# in3ator_LEDStrip2.net
KiCad netlist of a schematic drawn in Altium Designer
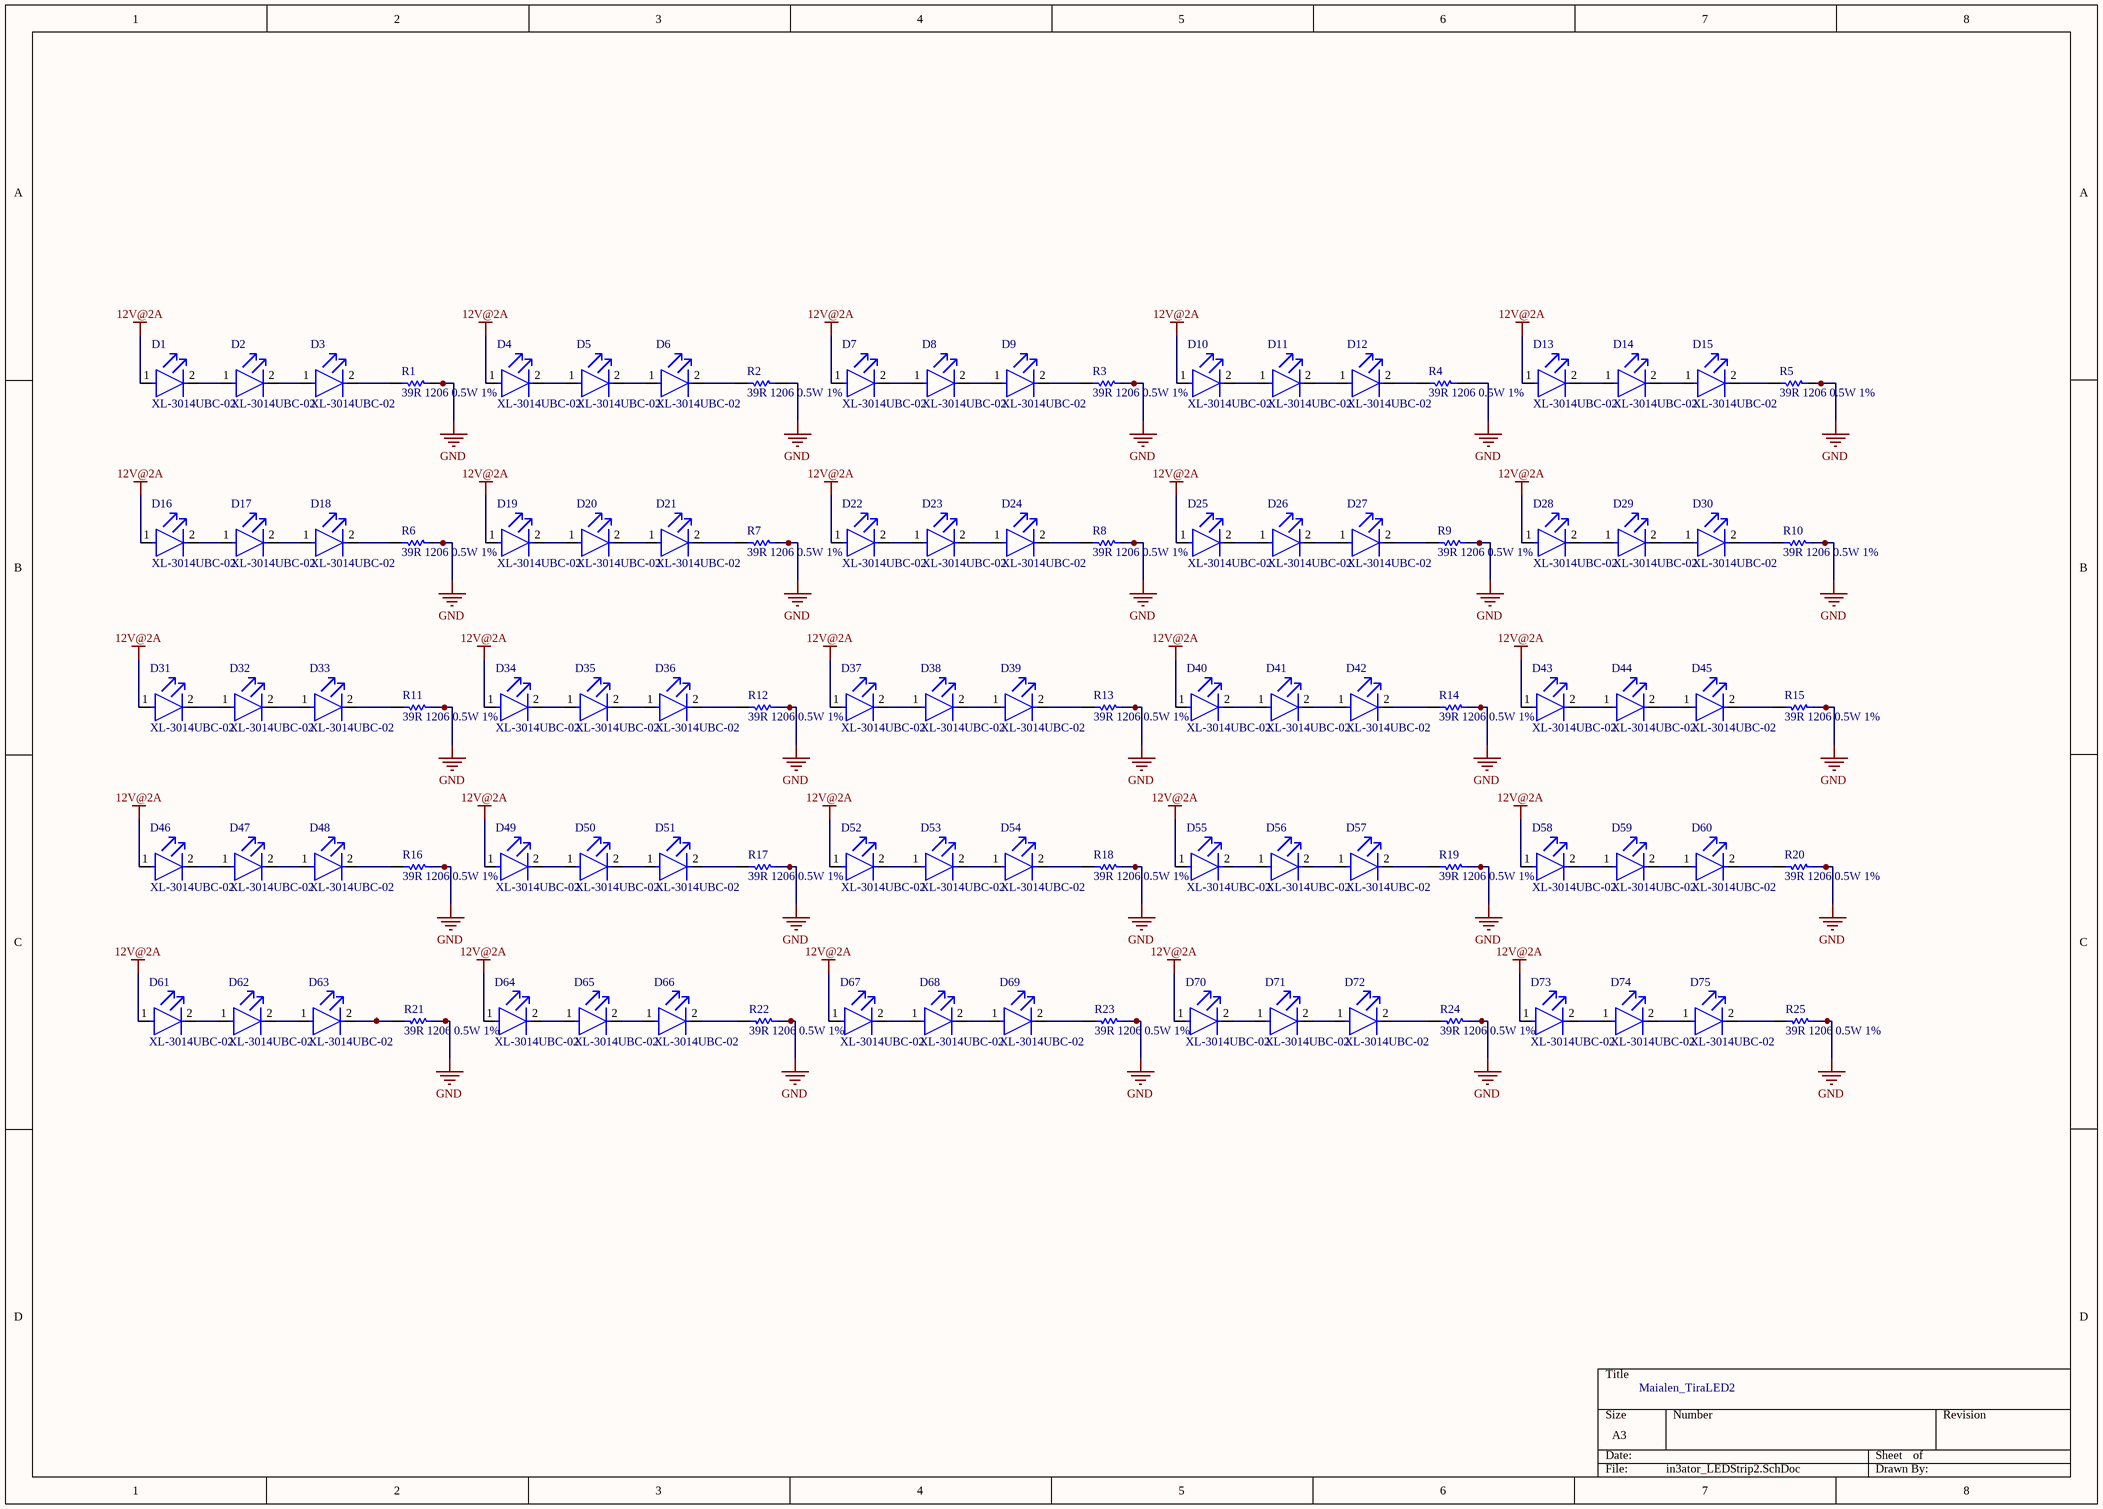
[diagram p0: in3ator_LEDStrip2.SchDoc]

(export (version "E")
  (design (tool "Eeschema 10.0.6"))
  (components
    (comp (ref "D1")
      (value "XL-3014UBC-02")
      (footprint "Diode_led")
      (description "LED GREEN ESS II SMD")
      (fields (field (name "OBSOLETE PART") "true") (field (name "MANUFACTURER") "Panasonic"))
      (libsource (lib "Maialen_TiraLED") (part "CMP-05535-000002-1"))
    )
    (comp (ref "D2")
      (value "XL-3014UBC-02")
      (footprint "Diode_led")
      (description "LED GREEN ESS II SMD")
      (fields (field (name "OBSOLETE PART") "true") (field (name "MANUFACTURER") "Panasonic"))
      (libsource (lib "Maialen_TiraLED") (part "CMP-05535-000002-1"))
    )
    (comp (ref "D3")
      (value "XL-3014UBC-02")
      (footprint "Diode_led")
      (description "LED GREEN ESS II SMD")
      (fields (field (name "OBSOLETE PART") "true") (field (name "MANUFACTURER") "Panasonic"))
      (libsource (lib "Maialen_TiraLED") (part "CMP-05535-000002-1"))
    )
    (comp (ref "D4")
      (value "XL-3014UBC-02")
      (footprint "Diode_led")
      (description "LED GREEN ESS II SMD")
      (fields (field (name "OBSOLETE PART") "true") (field (name "MANUFACTURER") "Panasonic"))
      (libsource (lib "Maialen_TiraLED") (part "CMP-05535-000002-1"))
    )
    (comp (ref "D5")
      (value "XL-3014UBC-02")
      (footprint "Diode_led")
      (description "LED GREEN ESS II SMD")
      (fields (field (name "OBSOLETE PART") "true") (field (name "MANUFACTURER") "Panasonic"))
      (libsource (lib "Maialen_TiraLED") (part "CMP-05535-000002-1"))
    )
    (comp (ref "D6")
      (value "XL-3014UBC-02")
      (footprint "Diode_led")
      (description "LED GREEN ESS II SMD")
      (fields (field (name "OBSOLETE PART") "true") (field (name "MANUFACTURER") "Panasonic"))
      (libsource (lib "Maialen_TiraLED") (part "CMP-05535-000002-1"))
    )
    (comp (ref "D7")
      (value "XL-3014UBC-02")
      (footprint "Diode_led")
      (description "LED GREEN ESS II SMD")
      (fields (field (name "OBSOLETE PART") "true") (field (name "MANUFACTURER") "Panasonic"))
      (libsource (lib "Maialen_TiraLED") (part "CMP-05535-000002-1"))
    )
    (comp (ref "D8")
      (value "XL-3014UBC-02")
      (footprint "Diode_led")
      (description "LED GREEN ESS II SMD")
      (fields (field (name "OBSOLETE PART") "true") (field (name "MANUFACTURER") "Panasonic"))
      (libsource (lib "Maialen_TiraLED") (part "CMP-05535-000002-1"))
    )
    (comp (ref "D9")
      (value "XL-3014UBC-02")
      (footprint "Diode_led")
      (description "LED GREEN ESS II SMD")
      (fields (field (name "OBSOLETE PART") "true") (field (name "MANUFACTURER") "Panasonic"))
      (libsource (lib "Maialen_TiraLED") (part "CMP-05535-000002-1"))
    )
    (comp (ref "D10")
      (value "XL-3014UBC-02")
      (footprint "Diode_led")
      (description "LED GREEN ESS II SMD")
      (fields (field (name "OBSOLETE PART") "true") (field (name "MANUFACTURER") "Panasonic"))
      (libsource (lib "Maialen_TiraLED") (part "CMP-05535-000002-1"))
    )
    (comp (ref "D11")
      (value "XL-3014UBC-02")
      (footprint "Diode_led")
      (description "LED GREEN ESS II SMD")
      (fields (field (name "OBSOLETE PART") "true") (field (name "MANUFACTURER") "Panasonic"))
      (libsource (lib "Maialen_TiraLED") (part "CMP-05535-000002-1"))
    )
    (comp (ref "D12")
      (value "XL-3014UBC-02")
      (footprint "Diode_led")
      (description "LED GREEN ESS II SMD")
      (fields (field (name "OBSOLETE PART") "true") (field (name "MANUFACTURER") "Panasonic"))
      (libsource (lib "Maialen_TiraLED") (part "CMP-05535-000002-1"))
    )
    (comp (ref "D13")
      (value "XL-3014UBC-02")
      (footprint "Diode_led")
      (description "LED GREEN ESS II SMD")
      (fields (field (name "OBSOLETE PART") "true") (field (name "MANUFACTURER") "Panasonic"))
      (libsource (lib "Maialen_TiraLED") (part "CMP-05535-000002-1"))
    )
    (comp (ref "D14")
      (value "XL-3014UBC-02")
      (footprint "Diode_led")
      (description "LED GREEN ESS II SMD")
      (fields (field (name "OBSOLETE PART") "true") (field (name "MANUFACTURER") "Panasonic"))
      (libsource (lib "Maialen_TiraLED") (part "CMP-05535-000002-1"))
    )
    (comp (ref "D15")
      (value "XL-3014UBC-02")
      (footprint "Diode_led")
      (description "LED GREEN ESS II SMD")
      (fields (field (name "OBSOLETE PART") "true") (field (name "MANUFACTURER") "Panasonic"))
      (libsource (lib "Maialen_TiraLED") (part "CMP-05535-000002-1"))
    )
    (comp (ref "D16")
      (value "XL-3014UBC-02")
      (footprint "Diode_led")
      (description "LED GREEN ESS II SMD")
      (fields (field (name "OBSOLETE PART") "true") (field (name "MANUFACTURER") "Panasonic"))
      (libsource (lib "Maialen_TiraLED") (part "CMP-05535-000002-1"))
    )
    (comp (ref "D17")
      (value "XL-3014UBC-02")
      (footprint "Diode_led")
      (description "LED GREEN ESS II SMD")
      (fields (field (name "OBSOLETE PART") "true") (field (name "MANUFACTURER") "Panasonic"))
      (libsource (lib "Maialen_TiraLED") (part "CMP-05535-000002-1"))
    )
    (comp (ref "D18")
      (value "XL-3014UBC-02")
      (footprint "Diode_led")
      (description "LED GREEN ESS II SMD")
      (fields (field (name "OBSOLETE PART") "true") (field (name "MANUFACTURER") "Panasonic"))
      (libsource (lib "Maialen_TiraLED") (part "CMP-05535-000002-1"))
    )
    (comp (ref "D19")
      (value "XL-3014UBC-02")
      (footprint "Diode_led")
      (description "LED GREEN ESS II SMD")
      (fields (field (name "OBSOLETE PART") "true") (field (name "MANUFACTURER") "Panasonic"))
      (libsource (lib "Maialen_TiraLED") (part "CMP-05535-000002-1"))
    )
    (comp (ref "D20")
      (value "XL-3014UBC-02")
      (footprint "Diode_led")
      (description "LED GREEN ESS II SMD")
      (fields (field (name "OBSOLETE PART") "true") (field (name "MANUFACTURER") "Panasonic"))
      (libsource (lib "Maialen_TiraLED") (part "CMP-05535-000002-1"))
    )
    (comp (ref "D21")
      (value "XL-3014UBC-02")
      (footprint "Diode_led")
      (description "LED GREEN ESS II SMD")
      (fields (field (name "OBSOLETE PART") "true") (field (name "MANUFACTURER") "Panasonic"))
      (libsource (lib "Maialen_TiraLED") (part "CMP-05535-000002-1"))
    )
    (comp (ref "D22")
      (value "XL-3014UBC-02")
      (footprint "Diode_led")
      (description "LED GREEN ESS II SMD")
      (fields (field (name "OBSOLETE PART") "true") (field (name "MANUFACTURER") "Panasonic"))
      (libsource (lib "Maialen_TiraLED") (part "CMP-05535-000002-1"))
    )
    (comp (ref "D23")
      (value "XL-3014UBC-02")
      (footprint "Diode_led")
      (description "LED GREEN ESS II SMD")
      (fields (field (name "OBSOLETE PART") "true") (field (name "MANUFACTURER") "Panasonic"))
      (libsource (lib "Maialen_TiraLED") (part "CMP-05535-000002-1"))
    )
    (comp (ref "D24")
      (value "XL-3014UBC-02")
      (footprint "Diode_led")
      (description "LED GREEN ESS II SMD")
      (fields (field (name "OBSOLETE PART") "true") (field (name "MANUFACTURER") "Panasonic"))
      (libsource (lib "Maialen_TiraLED") (part "CMP-05535-000002-1"))
    )
    (comp (ref "D25")
      (value "XL-3014UBC-02")
      (footprint "Diode_led")
      (description "LED GREEN ESS II SMD")
      (fields (field (name "OBSOLETE PART") "true") (field (name "MANUFACTURER") "Panasonic"))
      (libsource (lib "Maialen_TiraLED") (part "CMP-05535-000002-1"))
    )
    (comp (ref "D26")
      (value "XL-3014UBC-02")
      (footprint "Diode_led")
      (description "LED GREEN ESS II SMD")
      (fields (field (name "OBSOLETE PART") "true") (field (name "MANUFACTURER") "Panasonic"))
      (libsource (lib "Maialen_TiraLED") (part "CMP-05535-000002-1"))
    )
    (comp (ref "D27")
      (value "XL-3014UBC-02")
      (footprint "Diode_led")
      (description "LED GREEN ESS II SMD")
      (fields (field (name "OBSOLETE PART") "true") (field (name "MANUFACTURER") "Panasonic"))
      (libsource (lib "Maialen_TiraLED") (part "CMP-05535-000002-1"))
    )
    (comp (ref "D28")
      (value "XL-3014UBC-02")
      (footprint "Diode_led")
      (description "LED GREEN ESS II SMD")
      (fields (field (name "OBSOLETE PART") "true") (field (name "MANUFACTURER") "Panasonic"))
      (libsource (lib "Maialen_TiraLED") (part "CMP-05535-000002-1"))
    )
    (comp (ref "D29")
      (value "XL-3014UBC-02")
      (footprint "Diode_led")
      (description "LED GREEN ESS II SMD")
      (fields (field (name "OBSOLETE PART") "true") (field (name "MANUFACTURER") "Panasonic"))
      (libsource (lib "Maialen_TiraLED") (part "CMP-05535-000002-1"))
    )
    (comp (ref "D30")
      (value "XL-3014UBC-02")
      (footprint "Diode_led")
      (description "LED GREEN ESS II SMD")
      (fields (field (name "OBSOLETE PART") "true") (field (name "MANUFACTURER") "Panasonic"))
      (libsource (lib "Maialen_TiraLED") (part "CMP-05535-000002-1"))
    )
    (comp (ref "D31")
      (value "XL-3014UBC-02")
      (footprint "Diode_led")
      (description "LED GREEN ESS II SMD")
      (fields (field (name "OBSOLETE PART") "true") (field (name "MANUFACTURER") "Panasonic"))
      (libsource (lib "Maialen_TiraLED") (part "CMP-05535-000002-1"))
    )
    (comp (ref "D32")
      (value "XL-3014UBC-02")
      (footprint "Diode_led")
      (description "LED GREEN ESS II SMD")
      (fields (field (name "OBSOLETE PART") "true") (field (name "MANUFACTURER") "Panasonic"))
      (libsource (lib "Maialen_TiraLED") (part "CMP-05535-000002-1"))
    )
    (comp (ref "D33")
      (value "XL-3014UBC-02")
      (footprint "Diode_led")
      (description "LED GREEN ESS II SMD")
      (fields (field (name "OBSOLETE PART") "true") (field (name "MANUFACTURER") "Panasonic"))
      (libsource (lib "Maialen_TiraLED") (part "CMP-05535-000002-1"))
    )
    (comp (ref "D34")
      (value "XL-3014UBC-02")
      (footprint "Diode_led")
      (description "LED GREEN ESS II SMD")
      (fields (field (name "OBSOLETE PART") "true") (field (name "MANUFACTURER") "Panasonic"))
      (libsource (lib "Maialen_TiraLED") (part "CMP-05535-000002-1"))
    )
    (comp (ref "D35")
      (value "XL-3014UBC-02")
      (footprint "Diode_led")
      (description "LED GREEN ESS II SMD")
      (fields (field (name "OBSOLETE PART") "true") (field (name "MANUFACTURER") "Panasonic"))
      (libsource (lib "Maialen_TiraLED") (part "CMP-05535-000002-1"))
    )
    (comp (ref "D36")
      (value "XL-3014UBC-02")
      (footprint "Diode_led")
      (description "LED GREEN ESS II SMD")
      (fields (field (name "OBSOLETE PART") "true") (field (name "MANUFACTURER") "Panasonic"))
      (libsource (lib "Maialen_TiraLED") (part "CMP-05535-000002-1"))
    )
    (comp (ref "D37")
      (value "XL-3014UBC-02")
      (footprint "Diode_led")
      (description "LED GREEN ESS II SMD")
      (fields (field (name "OBSOLETE PART") "true") (field (name "MANUFACTURER") "Panasonic"))
      (libsource (lib "Maialen_TiraLED") (part "CMP-05535-000002-1"))
    )
    (comp (ref "D38")
      (value "XL-3014UBC-02")
      (footprint "Diode_led")
      (description "LED GREEN ESS II SMD")
      (fields (field (name "OBSOLETE PART") "true") (field (name "MANUFACTURER") "Panasonic"))
      (libsource (lib "Maialen_TiraLED") (part "CMP-05535-000002-1"))
    )
    (comp (ref "D39")
      (value "XL-3014UBC-02")
      (footprint "Diode_led")
      (description "LED GREEN ESS II SMD")
      (fields (field (name "OBSOLETE PART") "true") (field (name "MANUFACTURER") "Panasonic"))
      (libsource (lib "Maialen_TiraLED") (part "CMP-05535-000002-1"))
    )
    (comp (ref "D40")
      (value "XL-3014UBC-02")
      (footprint "Diode_led")
      (description "LED GREEN ESS II SMD")
      (fields (field (name "OBSOLETE PART") "true") (field (name "MANUFACTURER") "Panasonic"))
      (libsource (lib "Maialen_TiraLED") (part "CMP-05535-000002-1"))
    )
    (comp (ref "D41")
      (value "XL-3014UBC-02")
      (footprint "Diode_led")
      (description "LED GREEN ESS II SMD")
      (fields (field (name "OBSOLETE PART") "true") (field (name "MANUFACTURER") "Panasonic"))
      (libsource (lib "Maialen_TiraLED") (part "CMP-05535-000002-1"))
    )
    (comp (ref "D42")
      (value "XL-3014UBC-02")
      (footprint "Diode_led")
      (description "LED GREEN ESS II SMD")
      (fields (field (name "OBSOLETE PART") "true") (field (name "MANUFACTURER") "Panasonic"))
      (libsource (lib "Maialen_TiraLED") (part "CMP-05535-000002-1"))
    )
    (comp (ref "D43")
      (value "XL-3014UBC-02")
      (footprint "Diode_led")
      (description "LED GREEN ESS II SMD")
      (fields (field (name "OBSOLETE PART") "true") (field (name "MANUFACTURER") "Panasonic"))
      (libsource (lib "Maialen_TiraLED") (part "CMP-05535-000002-1"))
    )
    (comp (ref "D44")
      (value "XL-3014UBC-02")
      (footprint "Diode_led")
      (description "LED GREEN ESS II SMD")
      (fields (field (name "OBSOLETE PART") "true") (field (name "MANUFACTURER") "Panasonic"))
      (libsource (lib "Maialen_TiraLED") (part "CMP-05535-000002-1"))
    )
    (comp (ref "D45")
      (value "XL-3014UBC-02")
      (footprint "Diode_led")
      (description "LED GREEN ESS II SMD")
      (fields (field (name "OBSOLETE PART") "true") (field (name "MANUFACTURER") "Panasonic"))
      (libsource (lib "Maialen_TiraLED") (part "CMP-05535-000002-1"))
    )
    (comp (ref "D46")
      (value "XL-3014UBC-02")
      (footprint "Diode_led")
      (description "LED GREEN ESS II SMD")
      (fields (field (name "OBSOLETE PART") "true") (field (name "MANUFACTURER") "Panasonic"))
      (libsource (lib "Maialen_TiraLED") (part "CMP-05535-000002-1"))
    )
    (comp (ref "D47")
      (value "XL-3014UBC-02")
      (footprint "Diode_led")
      (description "LED GREEN ESS II SMD")
      (fields (field (name "OBSOLETE PART") "true") (field (name "MANUFACTURER") "Panasonic"))
      (libsource (lib "Maialen_TiraLED") (part "CMP-05535-000002-1"))
    )
    (comp (ref "D48")
      (value "XL-3014UBC-02")
      (footprint "Diode_led")
      (description "LED GREEN ESS II SMD")
      (fields (field (name "OBSOLETE PART") "true") (field (name "MANUFACTURER") "Panasonic"))
      (libsource (lib "Maialen_TiraLED") (part "CMP-05535-000002-1"))
    )
    (comp (ref "D49")
      (value "XL-3014UBC-02")
      (footprint "Diode_led")
      (description "LED GREEN ESS II SMD")
      (fields (field (name "OBSOLETE PART") "true") (field (name "MANUFACTURER") "Panasonic"))
      (libsource (lib "Maialen_TiraLED") (part "CMP-05535-000002-1"))
    )
    (comp (ref "D50")
      (value "XL-3014UBC-02")
      (footprint "Diode_led")
      (description "LED GREEN ESS II SMD")
      (fields (field (name "OBSOLETE PART") "true") (field (name "MANUFACTURER") "Panasonic"))
      (libsource (lib "Maialen_TiraLED") (part "CMP-05535-000002-1"))
    )
    (comp (ref "D51")
      (value "XL-3014UBC-02")
      (footprint "Diode_led")
      (description "LED GREEN ESS II SMD")
      (fields (field (name "OBSOLETE PART") "true") (field (name "MANUFACTURER") "Panasonic"))
      (libsource (lib "Maialen_TiraLED") (part "CMP-05535-000002-1"))
    )
    (comp (ref "D52")
      (value "XL-3014UBC-02")
      (footprint "Diode_led")
      (description "LED GREEN ESS II SMD")
      (fields (field (name "OBSOLETE PART") "true") (field (name "MANUFACTURER") "Panasonic"))
      (libsource (lib "Maialen_TiraLED") (part "CMP-05535-000002-1"))
    )
    (comp (ref "D53")
      (value "XL-3014UBC-02")
      (footprint "Diode_led")
      (description "LED GREEN ESS II SMD")
      (fields (field (name "OBSOLETE PART") "true") (field (name "MANUFACTURER") "Panasonic"))
      (libsource (lib "Maialen_TiraLED") (part "CMP-05535-000002-1"))
    )
    (comp (ref "D54")
      (value "XL-3014UBC-02")
      (footprint "Diode_led")
      (description "LED GREEN ESS II SMD")
      (fields (field (name "OBSOLETE PART") "true") (field (name "MANUFACTURER") "Panasonic"))
      (libsource (lib "Maialen_TiraLED") (part "CMP-05535-000002-1"))
    )
    (comp (ref "D55")
      (value "XL-3014UBC-02")
      (footprint "Diode_led")
      (description "LED GREEN ESS II SMD")
      (fields (field (name "OBSOLETE PART") "true") (field (name "MANUFACTURER") "Panasonic"))
      (libsource (lib "Maialen_TiraLED") (part "CMP-05535-000002-1"))
    )
    (comp (ref "D56")
      (value "XL-3014UBC-02")
      (footprint "Diode_led")
      (description "LED GREEN ESS II SMD")
      (fields (field (name "OBSOLETE PART") "true") (field (name "MANUFACTURER") "Panasonic"))
      (libsource (lib "Maialen_TiraLED") (part "CMP-05535-000002-1"))
    )
    (comp (ref "D57")
      (value "XL-3014UBC-02")
      (footprint "Diode_led")
      (description "LED GREEN ESS II SMD")
      (fields (field (name "OBSOLETE PART") "true") (field (name "MANUFACTURER") "Panasonic"))
      (libsource (lib "Maialen_TiraLED") (part "CMP-05535-000002-1"))
    )
    (comp (ref "D58")
      (value "XL-3014UBC-02")
      (footprint "Diode_led")
      (description "LED GREEN ESS II SMD")
      (fields (field (name "OBSOLETE PART") "true") (field (name "MANUFACTURER") "Panasonic"))
      (libsource (lib "Maialen_TiraLED") (part "CMP-05535-000002-1"))
    )
    (comp (ref "D59")
      (value "XL-3014UBC-02")
      (footprint "Diode_led")
      (description "LED GREEN ESS II SMD")
      (fields (field (name "OBSOLETE PART") "true") (field (name "MANUFACTURER") "Panasonic"))
      (libsource (lib "Maialen_TiraLED") (part "CMP-05535-000002-1"))
    )
    (comp (ref "D60")
      (value "XL-3014UBC-02")
      (footprint "Diode_led")
      (description "LED GREEN ESS II SMD")
      (fields (field (name "OBSOLETE PART") "true") (field (name "MANUFACTURER") "Panasonic"))
      (libsource (lib "Maialen_TiraLED") (part "CMP-05535-000002-1"))
    )
    (comp (ref "D61")
      (value "XL-3014UBC-02")
      (footprint "Diode_led")
      (description "LED GREEN ESS II SMD")
      (fields (field (name "OBSOLETE PART") "true") (field (name "MANUFACTURER") "Panasonic"))
      (libsource (lib "Maialen_TiraLED") (part "CMP-05535-000002-1"))
    )
    (comp (ref "D62")
      (value "XL-3014UBC-02")
      (footprint "Diode_led")
      (description "LED GREEN ESS II SMD")
      (fields (field (name "OBSOLETE PART") "true") (field (name "MANUFACTURER") "Panasonic"))
      (libsource (lib "Maialen_TiraLED") (part "CMP-05535-000002-1"))
    )
    (comp (ref "D63")
      (value "XL-3014UBC-02")
      (footprint "Diode_led")
      (description "LED GREEN ESS II SMD")
      (fields (field (name "OBSOLETE PART") "true") (field (name "MANUFACTURER") "Panasonic"))
      (libsource (lib "Maialen_TiraLED") (part "CMP-05535-000002-1"))
    )
    (comp (ref "D64")
      (value "XL-3014UBC-02")
      (footprint "Diode_led")
      (description "LED GREEN ESS II SMD")
      (fields (field (name "OBSOLETE PART") "true") (field (name "MANUFACTURER") "Panasonic"))
      (libsource (lib "Maialen_TiraLED") (part "CMP-05535-000002-1"))
    )
    (comp (ref "D65")
      (value "XL-3014UBC-02")
      (footprint "Diode_led")
      (description "LED GREEN ESS II SMD")
      (fields (field (name "OBSOLETE PART") "true") (field (name "MANUFACTURER") "Panasonic"))
      (libsource (lib "Maialen_TiraLED") (part "CMP-05535-000002-1"))
    )
    (comp (ref "D66")
      (value "XL-3014UBC-02")
      (footprint "Diode_led")
      (description "LED GREEN ESS II SMD")
      (fields (field (name "OBSOLETE PART") "true") (field (name "MANUFACTURER") "Panasonic"))
      (libsource (lib "Maialen_TiraLED") (part "CMP-05535-000002-1"))
    )
    (comp (ref "D67")
      (value "XL-3014UBC-02")
      (footprint "Diode_led")
      (description "LED GREEN ESS II SMD")
      (fields (field (name "OBSOLETE PART") "true") (field (name "MANUFACTURER") "Panasonic"))
      (libsource (lib "Maialen_TiraLED") (part "CMP-05535-000002-1"))
    )
    (comp (ref "D68")
      (value "XL-3014UBC-02")
      (footprint "Diode_led")
      (description "LED GREEN ESS II SMD")
      (fields (field (name "OBSOLETE PART") "true") (field (name "MANUFACTURER") "Panasonic"))
      (libsource (lib "Maialen_TiraLED") (part "CMP-05535-000002-1"))
    )
    (comp (ref "D69")
      (value "XL-3014UBC-02")
      (footprint "Diode_led")
      (description "LED GREEN ESS II SMD")
      (fields (field (name "OBSOLETE PART") "true") (field (name "MANUFACTURER") "Panasonic"))
      (libsource (lib "Maialen_TiraLED") (part "CMP-05535-000002-1"))
    )
    (comp (ref "D70")
      (value "XL-3014UBC-02")
      (footprint "Diode_led")
      (description "LED GREEN ESS II SMD")
      (fields (field (name "OBSOLETE PART") "true") (field (name "MANUFACTURER") "Panasonic"))
      (libsource (lib "Maialen_TiraLED") (part "CMP-05535-000002-1"))
    )
    (comp (ref "D71")
      (value "XL-3014UBC-02")
      (footprint "Diode_led")
      (description "LED GREEN ESS II SMD")
      (fields (field (name "OBSOLETE PART") "true") (field (name "MANUFACTURER") "Panasonic"))
      (libsource (lib "Maialen_TiraLED") (part "CMP-05535-000002-1"))
    )
    (comp (ref "D72")
      (value "XL-3014UBC-02")
      (footprint "Diode_led")
      (description "LED GREEN ESS II SMD")
      (fields (field (name "OBSOLETE PART") "true") (field (name "MANUFACTURER") "Panasonic"))
      (libsource (lib "Maialen_TiraLED") (part "CMP-05535-000002-1"))
    )
    (comp (ref "D73")
      (value "XL-3014UBC-02")
      (footprint "Diode_led")
      (description "LED GREEN ESS II SMD")
      (fields (field (name "OBSOLETE PART") "true") (field (name "MANUFACTURER") "Panasonic"))
      (libsource (lib "Maialen_TiraLED") (part "CMP-05535-000002-1"))
    )
    (comp (ref "D74")
      (value "XL-3014UBC-02")
      (footprint "Diode_led")
      (description "LED GREEN ESS II SMD")
      (fields (field (name "OBSOLETE PART") "true") (field (name "MANUFACTURER") "Panasonic"))
      (libsource (lib "Maialen_TiraLED") (part "CMP-05535-000002-1"))
    )
    (comp (ref "D75")
      (value "XL-3014UBC-02")
      (footprint "Diode_led")
      (description "LED GREEN ESS II SMD")
      (fields (field (name "OBSOLETE PART") "true") (field (name "MANUFACTURER") "Panasonic"))
      (libsource (lib "Maialen_TiraLED") (part "CMP-05535-000002-1"))
    )
    (comp (ref "R1")
      (value "39R 1206 0.5W 1%")
      (footprint "CAPC3216X180X55ML20T25")
      (fields (field (name "MANUFACTURER PART NUMBER") "WSLP12065L000FEA") (field (name "POWER") "1W"))
      (libsource (lib "in3ator") (part "CMP-0abdc173b10ad57a-1"))
    )
    (comp (ref "R2")
      (value "39R 1206 0.5W 1%")
      (footprint "CAPC3216X180X55ML20T25")
      (fields (field (name "MANUFACTURER PART NUMBER") "WSLP12065L000FEA") (field (name "POWER") "1W"))
      (libsource (lib "in3ator") (part "CMP-0abdc173b10ad57a-1"))
    )
    (comp (ref "R3")
      (value "39R 1206 0.5W 1%")
      (footprint "CAPC3216X180X55ML20T25")
      (fields (field (name "MANUFACTURER PART NUMBER") "WSLP12065L000FEA") (field (name "POWER") "1W"))
      (libsource (lib "in3ator") (part "CMP-0abdc173b10ad57a-1"))
    )
    (comp (ref "R4")
      (value "39R 1206 0.5W 1%")
      (footprint "CAPC3216X180X55ML20T25")
      (fields (field (name "MANUFACTURER PART NUMBER") "WSLP12065L000FEA") (field (name "POWER") "1W"))
      (libsource (lib "in3ator") (part "CMP-0abdc173b10ad57a-1"))
    )
    (comp (ref "R5")
      (value "39R 1206 0.5W 1%")
      (footprint "CAPC3216X180X55ML20T25")
      (fields (field (name "MANUFACTURER PART NUMBER") "WSLP12065L000FEA") (field (name "POWER") "1W"))
      (libsource (lib "in3ator") (part "CMP-0abdc173b10ad57a-1"))
    )
    (comp (ref "R6")
      (value "39R 1206 0.5W 1%")
      (footprint "CAPC3216X180X55ML20T25")
      (fields (field (name "MANUFACTURER PART NUMBER") "WSLP12065L000FEA") (field (name "POWER") "1W"))
      (libsource (lib "in3ator") (part "CMP-0abdc173b10ad57a-1"))
    )
    (comp (ref "R7")
      (value "39R 1206 0.5W 1%")
      (footprint "CAPC3216X180X55ML20T25")
      (fields (field (name "MANUFACTURER PART NUMBER") "WSLP12065L000FEA") (field (name "POWER") "1W"))
      (libsource (lib "in3ator") (part "CMP-0abdc173b10ad57a-1"))
    )
    (comp (ref "R8")
      (value "39R 1206 0.5W 1%")
      (footprint "CAPC3216X180X55ML20T25")
      (fields (field (name "MANUFACTURER PART NUMBER") "WSLP12065L000FEA") (field (name "POWER") "1W"))
      (libsource (lib "in3ator") (part "CMP-0abdc173b10ad57a-1"))
    )
    (comp (ref "R9")
      (value "39R 1206 0.5W 1%")
      (footprint "CAPC3216X180X55ML20T25")
      (fields (field (name "MANUFACTURER PART NUMBER") "WSLP12065L000FEA") (field (name "POWER") "1W"))
      (libsource (lib "in3ator") (part "CMP-0abdc173b10ad57a-1"))
    )
    (comp (ref "R10")
      (value "39R 1206 0.5W 1%")
      (footprint "CAPC3216X180X55ML20T25")
      (fields (field (name "MANUFACTURER PART NUMBER") "WSLP12065L000FEA") (field (name "POWER") "1W"))
      (libsource (lib "in3ator") (part "CMP-0abdc173b10ad57a-1"))
    )
    (comp (ref "R11")
      (value "39R 1206 0.5W 1%")
      (footprint "CAPC3216X180X55ML20T25")
      (fields (field (name "MANUFACTURER PART NUMBER") "WSLP12065L000FEA") (field (name "POWER") "1W"))
      (libsource (lib "in3ator") (part "CMP-0abdc173b10ad57a-1"))
    )
    (comp (ref "R12")
      (value "39R 1206 0.5W 1%")
      (footprint "CAPC3216X180X55ML20T25")
      (fields (field (name "MANUFACTURER PART NUMBER") "WSLP12065L000FEA") (field (name "POWER") "1W"))
      (libsource (lib "in3ator") (part "CMP-0abdc173b10ad57a-1"))
    )
    (comp (ref "R13")
      (value "39R 1206 0.5W 1%")
      (footprint "CAPC3216X180X55ML20T25")
      (fields (field (name "MANUFACTURER PART NUMBER") "WSLP12065L000FEA") (field (name "POWER") "1W"))
      (libsource (lib "in3ator") (part "CMP-0abdc173b10ad57a-1"))
    )
    (comp (ref "R14")
      (value "39R 1206 0.5W 1%")
      (footprint "CAPC3216X180X55ML20T25")
      (fields (field (name "MANUFACTURER PART NUMBER") "WSLP12065L000FEA") (field (name "POWER") "1W"))
      (libsource (lib "in3ator") (part "CMP-0abdc173b10ad57a-1"))
    )
    (comp (ref "R15")
      (value "39R 1206 0.5W 1%")
      (footprint "CAPC3216X180X55ML20T25")
      (fields (field (name "MANUFACTURER PART NUMBER") "WSLP12065L000FEA") (field (name "POWER") "1W"))
      (libsource (lib "in3ator") (part "CMP-0abdc173b10ad57a-1"))
    )
    (comp (ref "R16")
      (value "39R 1206 0.5W 1%")
      (footprint "CAPC3216X180X55ML20T25")
      (fields (field (name "MANUFACTURER PART NUMBER") "WSLP12065L000FEA") (field (name "POWER") "1W"))
      (libsource (lib "in3ator") (part "CMP-0abdc173b10ad57a-1"))
    )
    (comp (ref "R17")
      (value "39R 1206 0.5W 1%")
      (footprint "CAPC3216X180X55ML20T25")
      (fields (field (name "MANUFACTURER PART NUMBER") "WSLP12065L000FEA") (field (name "POWER") "1W"))
      (libsource (lib "in3ator") (part "CMP-0abdc173b10ad57a-1"))
    )
    (comp (ref "R18")
      (value "39R 1206 0.5W 1%")
      (footprint "CAPC3216X180X55ML20T25")
      (fields (field (name "MANUFACTURER PART NUMBER") "WSLP12065L000FEA") (field (name "POWER") "1W"))
      (libsource (lib "in3ator") (part "CMP-0abdc173b10ad57a-1"))
    )
    (comp (ref "R19")
      (value "39R 1206 0.5W 1%")
      (footprint "CAPC3216X180X55ML20T25")
      (fields (field (name "MANUFACTURER PART NUMBER") "WSLP12065L000FEA") (field (name "POWER") "1W"))
      (libsource (lib "in3ator") (part "CMP-0abdc173b10ad57a-1"))
    )
    (comp (ref "R20")
      (value "39R 1206 0.5W 1%")
      (footprint "CAPC3216X180X55ML20T25")
      (fields (field (name "MANUFACTURER PART NUMBER") "WSLP12065L000FEA") (field (name "POWER") "1W"))
      (libsource (lib "in3ator") (part "CMP-0abdc173b10ad57a-1"))
    )
    (comp (ref "R21")
      (value "39R 1206 0.5W 1%")
      (footprint "CAPC3216X180X55ML20T25")
      (fields (field (name "MANUFACTURER PART NUMBER") "WSLP12065L000FEA") (field (name "POWER") "1W"))
      (libsource (lib "in3ator") (part "CMP-0abdc173b10ad57a-1"))
    )
    (comp (ref "R22")
      (value "39R 1206 0.5W 1%")
      (footprint "CAPC3216X180X55ML20T25")
      (fields (field (name "MANUFACTURER PART NUMBER") "WSLP12065L000FEA") (field (name "POWER") "1W"))
      (libsource (lib "in3ator") (part "CMP-0abdc173b10ad57a-1"))
    )
    (comp (ref "R23")
      (value "39R 1206 0.5W 1%")
      (footprint "CAPC3216X180X55ML20T25")
      (fields (field (name "MANUFACTURER PART NUMBER") "WSLP12065L000FEA") (field (name "POWER") "1W"))
      (libsource (lib "in3ator") (part "CMP-0abdc173b10ad57a-1"))
    )
    (comp (ref "R24")
      (value "39R 1206 0.5W 1%")
      (footprint "CAPC3216X180X55ML20T25")
      (fields (field (name "MANUFACTURER PART NUMBER") "WSLP12065L000FEA") (field (name "POWER") "1W"))
      (libsource (lib "in3ator") (part "CMP-0abdc173b10ad57a-1"))
    )
    (comp (ref "R25")
      (value "39R 1206 0.5W 1%")
      (footprint "CAPC3216X180X55ML20T25")
      (fields (field (name "MANUFACTURER PART NUMBER") "WSLP12065L000FEA") (field (name "POWER") "1W"))
      (libsource (lib "in3ator") (part "CMP-0abdc173b10ad57a-1"))
    )
  )
  (nets
    (net (code "1") (name "12V@2A") (class "Default")
      (node (ref "D1") (pin "1") (pinfunction "A_1") (pintype "passive"))
      (node (ref "D10") (pin "1") (pinfunction "A_1") (pintype "passive"))
      (node (ref "D13") (pin "1") (pinfunction "A_1") (pintype "passive"))
      (node (ref "D16") (pin "1") (pinfunction "A_1") (pintype "passive"))
      (node (ref "D19") (pin "1") (pinfunction "A_1") (pintype "passive"))
      (node (ref "D22") (pin "1") (pinfunction "A_1") (pintype "passive"))
      (node (ref "D25") (pin "1") (pinfunction "A_1") (pintype "passive"))
      (node (ref "D28") (pin "1") (pinfunction "A_1") (pintype "passive"))
      (node (ref "D31") (pin "1") (pinfunction "A_1") (pintype "passive"))
      (node (ref "D34") (pin "1") (pinfunction "A_1") (pintype "passive"))
      (node (ref "D37") (pin "1") (pinfunction "A_1") (pintype "passive"))
      (node (ref "D4") (pin "1") (pinfunction "A_1") (pintype "passive"))
      (node (ref "D40") (pin "1") (pinfunction "A_1") (pintype "passive"))
      (node (ref "D43") (pin "1") (pinfunction "A_1") (pintype "passive"))
      (node (ref "D46") (pin "1") (pinfunction "A_1") (pintype "passive"))
      (node (ref "D49") (pin "1") (pinfunction "A_1") (pintype "passive"))
      (node (ref "D52") (pin "1") (pinfunction "A_1") (pintype "passive"))
      (node (ref "D55") (pin "1") (pinfunction "A_1") (pintype "passive"))
      (node (ref "D58") (pin "1") (pinfunction "A_1") (pintype "passive"))
      (node (ref "D61") (pin "1") (pinfunction "A_1") (pintype "passive"))
      (node (ref "D64") (pin "1") (pinfunction "A_1") (pintype "passive"))
      (node (ref "D67") (pin "1") (pinfunction "A_1") (pintype "passive"))
      (node (ref "D7") (pin "1") (pinfunction "A_1") (pintype "passive"))
      (node (ref "D70") (pin "1") (pinfunction "A_1") (pintype "passive"))
      (node (ref "D73") (pin "1") (pinfunction "A_1") (pintype "passive"))
    )
    (net (code "2") (name "GND") (class "Default")
      (node (ref "R1") (pin "2") (pinfunction "2_2") (pintype "passive"))
      (node (ref "R10") (pin "2") (pinfunction "2_2") (pintype "passive"))
      (node (ref "R11") (pin "2") (pinfunction "2_2") (pintype "passive"))
      (node (ref "R12") (pin "2") (pinfunction "2_2") (pintype "passive"))
      (node (ref "R13") (pin "2") (pinfunction "2_2") (pintype "passive"))
      (node (ref "R14") (pin "2") (pinfunction "2_2") (pintype "passive"))
      (node (ref "R15") (pin "2") (pinfunction "2_2") (pintype "passive"))
      (node (ref "R16") (pin "2") (pinfunction "2_2") (pintype "passive"))
      (node (ref "R17") (pin "2") (pinfunction "2_2") (pintype "passive"))
      (node (ref "R18") (pin "2") (pinfunction "2_2") (pintype "passive"))
      (node (ref "R19") (pin "2") (pinfunction "2_2") (pintype "passive"))
      (node (ref "R2") (pin "2") (pinfunction "2_2") (pintype "passive"))
      (node (ref "R20") (pin "2") (pinfunction "2_2") (pintype "passive"))
      (node (ref "R21") (pin "2") (pinfunction "2_2") (pintype "passive"))
      (node (ref "R22") (pin "2") (pinfunction "2_2") (pintype "passive"))
      (node (ref "R23") (pin "2") (pinfunction "2_2") (pintype "passive"))
      (node (ref "R24") (pin "2") (pinfunction "2_2") (pintype "passive"))
      (node (ref "R25") (pin "2") (pinfunction "2_2") (pintype "passive"))
      (node (ref "R3") (pin "2") (pinfunction "2_2") (pintype "passive"))
      (node (ref "R4") (pin "2") (pinfunction "2_2") (pintype "passive"))
      (node (ref "R5") (pin "2") (pinfunction "2_2") (pintype "passive"))
      (node (ref "R6") (pin "2") (pinfunction "2_2") (pintype "passive"))
      (node (ref "R7") (pin "2") (pinfunction "2_2") (pintype "passive"))
      (node (ref "R8") (pin "2") (pinfunction "2_2") (pintype "passive"))
      (node (ref "R9") (pin "2") (pinfunction "2_2") (pintype "passive"))
    )
    (net (code "3") (name "Net-(D1-C)") (class "Default")
      (node (ref "D1") (pin "2") (pinfunction "C_2") (pintype "passive"))
      (node (ref "D2") (pin "1") (pinfunction "A_1") (pintype "passive"))
    )
    (net (code "4") (name "Net-(D2-C)") (class "Default")
      (node (ref "D2") (pin "2") (pinfunction "C_2") (pintype "passive"))
      (node (ref "D3") (pin "1") (pinfunction "A_1") (pintype "passive"))
    )
    (net (code "5") (name "Net-(D3-C)") (class "Default")
      (node (ref "D3") (pin "2") (pinfunction "C_2") (pintype "passive"))
      (node (ref "R1") (pin "1") (pinfunction "1_1") (pintype "passive"))
    )
    (net (code "6") (name "Net-(D4-C)") (class "Default")
      (node (ref "D4") (pin "2") (pinfunction "C_2") (pintype "passive"))
      (node (ref "D5") (pin "1") (pinfunction "A_1") (pintype "passive"))
    )
    (net (code "7") (name "Net-(D5-C)") (class "Default")
      (node (ref "D5") (pin "2") (pinfunction "C_2") (pintype "passive"))
      (node (ref "D6") (pin "1") (pinfunction "A_1") (pintype "passive"))
    )
    (net (code "8") (name "Net-(D6-C)") (class "Default")
      (node (ref "D6") (pin "2") (pinfunction "C_2") (pintype "passive"))
      (node (ref "R2") (pin "1") (pinfunction "1_1") (pintype "passive"))
    )
    (net (code "9") (name "Net-(D7-C)") (class "Default")
      (node (ref "D7") (pin "2") (pinfunction "C_2") (pintype "passive"))
      (node (ref "D8") (pin "1") (pinfunction "A_1") (pintype "passive"))
    )
    (net (code "10") (name "Net-(D8-C)") (class "Default")
      (node (ref "D8") (pin "2") (pinfunction "C_2") (pintype "passive"))
      (node (ref "D9") (pin "1") (pinfunction "A_1") (pintype "passive"))
    )
    (net (code "11") (name "Net-(D9-C)") (class "Default")
      (node (ref "D9") (pin "2") (pinfunction "C_2") (pintype "passive"))
      (node (ref "R3") (pin "1") (pinfunction "1_1") (pintype "passive"))
    )
    (net (code "12") (name "Net-(D10-C)") (class "Default")
      (node (ref "D10") (pin "2") (pinfunction "C_2") (pintype "passive"))
      (node (ref "D11") (pin "1") (pinfunction "A_1") (pintype "passive"))
    )
    (net (code "13") (name "Net-(D11-C)") (class "Default")
      (node (ref "D11") (pin "2") (pinfunction "C_2") (pintype "passive"))
      (node (ref "D12") (pin "1") (pinfunction "A_1") (pintype "passive"))
    )
    (net (code "14") (name "Net-(D12-C)") (class "Default")
      (node (ref "D12") (pin "2") (pinfunction "C_2") (pintype "passive"))
      (node (ref "R4") (pin "1") (pinfunction "1_1") (pintype "passive"))
    )
    (net (code "15") (name "Net-(D13-C)") (class "Default")
      (node (ref "D13") (pin "2") (pinfunction "C_2") (pintype "passive"))
      (node (ref "D14") (pin "1") (pinfunction "A_1") (pintype "passive"))
    )
    (net (code "16") (name "Net-(D14-C)") (class "Default")
      (node (ref "D14") (pin "2") (pinfunction "C_2") (pintype "passive"))
      (node (ref "D15") (pin "1") (pinfunction "A_1") (pintype "passive"))
    )
    (net (code "17") (name "Net-(D15-C)") (class "Default")
      (node (ref "D15") (pin "2") (pinfunction "C_2") (pintype "passive"))
      (node (ref "R5") (pin "1") (pinfunction "1_1") (pintype "passive"))
    )
    (net (code "18") (name "Net-(D16-C)") (class "Default")
      (node (ref "D16") (pin "2") (pinfunction "C_2") (pintype "passive"))
      (node (ref "D17") (pin "1") (pinfunction "A_1") (pintype "passive"))
    )
    (net (code "19") (name "Net-(D17-C)") (class "Default")
      (node (ref "D17") (pin "2") (pinfunction "C_2") (pintype "passive"))
      (node (ref "D18") (pin "1") (pinfunction "A_1") (pintype "passive"))
    )
    (net (code "20") (name "Net-(D18-C)") (class "Default")
      (node (ref "D18") (pin "2") (pinfunction "C_2") (pintype "passive"))
      (node (ref "R6") (pin "1") (pinfunction "1_1") (pintype "passive"))
    )
    (net (code "21") (name "Net-(D19-C)") (class "Default")
      (node (ref "D19") (pin "2") (pinfunction "C_2") (pintype "passive"))
      (node (ref "D20") (pin "1") (pinfunction "A_1") (pintype "passive"))
    )
    (net (code "22") (name "Net-(D20-C)") (class "Default")
      (node (ref "D20") (pin "2") (pinfunction "C_2") (pintype "passive"))
      (node (ref "D21") (pin "1") (pinfunction "A_1") (pintype "passive"))
    )
    (net (code "23") (name "Net-(D21-C)") (class "Default")
      (node (ref "D21") (pin "2") (pinfunction "C_2") (pintype "passive"))
      (node (ref "R7") (pin "1") (pinfunction "1_1") (pintype "passive"))
    )
    (net (code "24") (name "Net-(D22-C)") (class "Default")
      (node (ref "D22") (pin "2") (pinfunction "C_2") (pintype "passive"))
      (node (ref "D23") (pin "1") (pinfunction "A_1") (pintype "passive"))
    )
    (net (code "25") (name "Net-(D23-C)") (class "Default")
      (node (ref "D23") (pin "2") (pinfunction "C_2") (pintype "passive"))
      (node (ref "D24") (pin "1") (pinfunction "A_1") (pintype "passive"))
    )
    (net (code "26") (name "Net-(D24-C)") (class "Default")
      (node (ref "D24") (pin "2") (pinfunction "C_2") (pintype "passive"))
      (node (ref "R8") (pin "1") (pinfunction "1_1") (pintype "passive"))
    )
    (net (code "27") (name "Net-(D25-C)") (class "Default")
      (node (ref "D25") (pin "2") (pinfunction "C_2") (pintype "passive"))
      (node (ref "D26") (pin "1") (pinfunction "A_1") (pintype "passive"))
    )
    (net (code "28") (name "Net-(D26-C)") (class "Default")
      (node (ref "D26") (pin "2") (pinfunction "C_2") (pintype "passive"))
      (node (ref "D27") (pin "1") (pinfunction "A_1") (pintype "passive"))
    )
    (net (code "29") (name "Net-(D27-C)") (class "Default")
      (node (ref "D27") (pin "2") (pinfunction "C_2") (pintype "passive"))
      (node (ref "R9") (pin "1") (pinfunction "1_1") (pintype "passive"))
    )
    (net (code "30") (name "Net-(D28-C)") (class "Default")
      (node (ref "D28") (pin "2") (pinfunction "C_2") (pintype "passive"))
      (node (ref "D29") (pin "1") (pinfunction "A_1") (pintype "passive"))
    )
    (net (code "31") (name "Net-(D29-C)") (class "Default")
      (node (ref "D29") (pin "2") (pinfunction "C_2") (pintype "passive"))
      (node (ref "D30") (pin "1") (pinfunction "A_1") (pintype "passive"))
    )
    (net (code "32") (name "Net-(D30-C)") (class "Default")
      (node (ref "D30") (pin "2") (pinfunction "C_2") (pintype "passive"))
      (node (ref "R10") (pin "1") (pinfunction "1_1") (pintype "passive"))
    )
    (net (code "33") (name "Net-(D31-C)") (class "Default")
      (node (ref "D31") (pin "2") (pinfunction "C_2") (pintype "passive"))
      (node (ref "D32") (pin "1") (pinfunction "A_1") (pintype "passive"))
    )
    (net (code "34") (name "Net-(D32-C)") (class "Default")
      (node (ref "D32") (pin "2") (pinfunction "C_2") (pintype "passive"))
      (node (ref "D33") (pin "1") (pinfunction "A_1") (pintype "passive"))
    )
    (net (code "35") (name "Net-(D33-C)") (class "Default")
      (node (ref "D33") (pin "2") (pinfunction "C_2") (pintype "passive"))
      (node (ref "R11") (pin "1") (pinfunction "1_1") (pintype "passive"))
    )
    (net (code "36") (name "Net-(D34-C)") (class "Default")
      (node (ref "D34") (pin "2") (pinfunction "C_2") (pintype "passive"))
      (node (ref "D35") (pin "1") (pinfunction "A_1") (pintype "passive"))
    )
    (net (code "37") (name "Net-(D35-C)") (class "Default")
      (node (ref "D35") (pin "2") (pinfunction "C_2") (pintype "passive"))
      (node (ref "D36") (pin "1") (pinfunction "A_1") (pintype "passive"))
    )
    (net (code "38") (name "Net-(D36-C)") (class "Default")
      (node (ref "D36") (pin "2") (pinfunction "C_2") (pintype "passive"))
      (node (ref "R12") (pin "1") (pinfunction "1_1") (pintype "passive"))
    )
    (net (code "39") (name "Net-(D37-C)") (class "Default")
      (node (ref "D37") (pin "2") (pinfunction "C_2") (pintype "passive"))
      (node (ref "D38") (pin "1") (pinfunction "A_1") (pintype "passive"))
    )
    (net (code "40") (name "Net-(D38-C)") (class "Default")
      (node (ref "D38") (pin "2") (pinfunction "C_2") (pintype "passive"))
      (node (ref "D39") (pin "1") (pinfunction "A_1") (pintype "passive"))
    )
    (net (code "41") (name "Net-(D39-C)") (class "Default")
      (node (ref "D39") (pin "2") (pinfunction "C_2") (pintype "passive"))
      (node (ref "R13") (pin "1") (pinfunction "1_1") (pintype "passive"))
    )
    (net (code "42") (name "Net-(D40-C)") (class "Default")
      (node (ref "D40") (pin "2") (pinfunction "C_2") (pintype "passive"))
      (node (ref "D41") (pin "1") (pinfunction "A_1") (pintype "passive"))
    )
    (net (code "43") (name "Net-(D41-C)") (class "Default")
      (node (ref "D41") (pin "2") (pinfunction "C_2") (pintype "passive"))
      (node (ref "D42") (pin "1") (pinfunction "A_1") (pintype "passive"))
    )
    (net (code "44") (name "Net-(D42-C)") (class "Default")
      (node (ref "D42") (pin "2") (pinfunction "C_2") (pintype "passive"))
      (node (ref "R14") (pin "1") (pinfunction "1_1") (pintype "passive"))
    )
    (net (code "45") (name "Net-(D43-C)") (class "Default")
      (node (ref "D43") (pin "2") (pinfunction "C_2") (pintype "passive"))
      (node (ref "D44") (pin "1") (pinfunction "A_1") (pintype "passive"))
    )
    (net (code "46") (name "Net-(D44-C)") (class "Default")
      (node (ref "D44") (pin "2") (pinfunction "C_2") (pintype "passive"))
      (node (ref "D45") (pin "1") (pinfunction "A_1") (pintype "passive"))
    )
    (net (code "47") (name "Net-(D45-C)") (class "Default")
      (node (ref "D45") (pin "2") (pinfunction "C_2") (pintype "passive"))
      (node (ref "R15") (pin "1") (pinfunction "1_1") (pintype "passive"))
    )
    (net (code "48") (name "Net-(D46-C)") (class "Default")
      (node (ref "D46") (pin "2") (pinfunction "C_2") (pintype "passive"))
      (node (ref "D47") (pin "1") (pinfunction "A_1") (pintype "passive"))
    )
    (net (code "49") (name "Net-(D47-C)") (class "Default")
      (node (ref "D47") (pin "2") (pinfunction "C_2") (pintype "passive"))
      (node (ref "D48") (pin "1") (pinfunction "A_1") (pintype "passive"))
    )
    (net (code "50") (name "Net-(D48-C)") (class "Default")
      (node (ref "D48") (pin "2") (pinfunction "C_2") (pintype "passive"))
      (node (ref "R16") (pin "1") (pinfunction "1_1") (pintype "passive"))
    )
    (net (code "51") (name "Net-(D49-C)") (class "Default")
      (node (ref "D49") (pin "2") (pinfunction "C_2") (pintype "passive"))
      (node (ref "D50") (pin "1") (pinfunction "A_1") (pintype "passive"))
    )
    (net (code "52") (name "Net-(D50-C)") (class "Default")
      (node (ref "D50") (pin "2") (pinfunction "C_2") (pintype "passive"))
      (node (ref "D51") (pin "1") (pinfunction "A_1") (pintype "passive"))
    )
    (net (code "53") (name "Net-(D51-C)") (class "Default")
      (node (ref "D51") (pin "2") (pinfunction "C_2") (pintype "passive"))
      (node (ref "R17") (pin "1") (pinfunction "1_1") (pintype "passive"))
    )
    (net (code "54") (name "Net-(D52-C)") (class "Default")
      (node (ref "D52") (pin "2") (pinfunction "C_2") (pintype "passive"))
      (node (ref "D53") (pin "1") (pinfunction "A_1") (pintype "passive"))
    )
    (net (code "55") (name "Net-(D53-C)") (class "Default")
      (node (ref "D53") (pin "2") (pinfunction "C_2") (pintype "passive"))
      (node (ref "D54") (pin "1") (pinfunction "A_1") (pintype "passive"))
    )
    (net (code "56") (name "Net-(D54-C)") (class "Default")
      (node (ref "D54") (pin "2") (pinfunction "C_2") (pintype "passive"))
      (node (ref "R18") (pin "1") (pinfunction "1_1") (pintype "passive"))
    )
    (net (code "57") (name "Net-(D55-C)") (class "Default")
      (node (ref "D55") (pin "2") (pinfunction "C_2") (pintype "passive"))
      (node (ref "D56") (pin "1") (pinfunction "A_1") (pintype "passive"))
    )
    (net (code "58") (name "Net-(D56-C)") (class "Default")
      (node (ref "D56") (pin "2") (pinfunction "C_2") (pintype "passive"))
      (node (ref "D57") (pin "1") (pinfunction "A_1") (pintype "passive"))
    )
    (net (code "59") (name "Net-(D57-C)") (class "Default")
      (node (ref "D57") (pin "2") (pinfunction "C_2") (pintype "passive"))
      (node (ref "R19") (pin "1") (pinfunction "1_1") (pintype "passive"))
    )
    (net (code "60") (name "Net-(D58-C)") (class "Default")
      (node (ref "D58") (pin "2") (pinfunction "C_2") (pintype "passive"))
      (node (ref "D59") (pin "1") (pinfunction "A_1") (pintype "passive"))
    )
    (net (code "61") (name "Net-(D59-C)") (class "Default")
      (node (ref "D59") (pin "2") (pinfunction "C_2") (pintype "passive"))
      (node (ref "D60") (pin "1") (pinfunction "A_1") (pintype "passive"))
    )
    (net (code "62") (name "Net-(D60-C)") (class "Default")
      (node (ref "D60") (pin "2") (pinfunction "C_2") (pintype "passive"))
      (node (ref "R20") (pin "1") (pinfunction "1_1") (pintype "passive"))
    )
    (net (code "63") (name "Net-(D61-C)") (class "Default")
      (node (ref "D61") (pin "2") (pinfunction "C_2") (pintype "passive"))
      (node (ref "D62") (pin "1") (pinfunction "A_1") (pintype "passive"))
    )
    (net (code "64") (name "Net-(D62-C)") (class "Default")
      (node (ref "D62") (pin "2") (pinfunction "C_2") (pintype "passive"))
      (node (ref "D63") (pin "1") (pinfunction "A_1") (pintype "passive"))
    )
    (net (code "65") (name "Net-(D63-C)") (class "Default")
      (node (ref "D63") (pin "2") (pinfunction "C_2") (pintype "passive"))
      (node (ref "R21") (pin "1") (pinfunction "1_1") (pintype "passive"))
    )
    (net (code "66") (name "Net-(D64-C)") (class "Default")
      (node (ref "D64") (pin "2") (pinfunction "C_2") (pintype "passive"))
      (node (ref "D65") (pin "1") (pinfunction "A_1") (pintype "passive"))
    )
    (net (code "67") (name "Net-(D65-C)") (class "Default")
      (node (ref "D65") (pin "2") (pinfunction "C_2") (pintype "passive"))
      (node (ref "D66") (pin "1") (pinfunction "A_1") (pintype "passive"))
    )
    (net (code "68") (name "Net-(D66-C)") (class "Default")
      (node (ref "D66") (pin "2") (pinfunction "C_2") (pintype "passive"))
      (node (ref "R22") (pin "1") (pinfunction "1_1") (pintype "passive"))
    )
    (net (code "69") (name "Net-(D67-C)") (class "Default")
      (node (ref "D67") (pin "2") (pinfunction "C_2") (pintype "passive"))
      (node (ref "D68") (pin "1") (pinfunction "A_1") (pintype "passive"))
    )
    (net (code "70") (name "Net-(D68-C)") (class "Default")
      (node (ref "D68") (pin "2") (pinfunction "C_2") (pintype "passive"))
      (node (ref "D69") (pin "1") (pinfunction "A_1") (pintype "passive"))
    )
    (net (code "71") (name "Net-(D69-C)") (class "Default")
      (node (ref "D69") (pin "2") (pinfunction "C_2") (pintype "passive"))
      (node (ref "R23") (pin "1") (pinfunction "1_1") (pintype "passive"))
    )
    (net (code "72") (name "Net-(D70-C)") (class "Default")
      (node (ref "D70") (pin "2") (pinfunction "C_2") (pintype "passive"))
      (node (ref "D71") (pin "1") (pinfunction "A_1") (pintype "passive"))
    )
    (net (code "73") (name "Net-(D71-C)") (class "Default")
      (node (ref "D71") (pin "2") (pinfunction "C_2") (pintype "passive"))
      (node (ref "D72") (pin "1") (pinfunction "A_1") (pintype "passive"))
    )
    (net (code "74") (name "Net-(D72-C)") (class "Default")
      (node (ref "D72") (pin "2") (pinfunction "C_2") (pintype "passive"))
      (node (ref "R24") (pin "1") (pinfunction "1_1") (pintype "passive"))
    )
    (net (code "75") (name "Net-(D73-C)") (class "Default")
      (node (ref "D73") (pin "2") (pinfunction "C_2") (pintype "passive"))
      (node (ref "D74") (pin "1") (pinfunction "A_1") (pintype "passive"))
    )
    (net (code "76") (name "Net-(D74-C)") (class "Default")
      (node (ref "D74") (pin "2") (pinfunction "C_2") (pintype "passive"))
      (node (ref "D75") (pin "1") (pinfunction "A_1") (pintype "passive"))
    )
    (net (code "77") (name "Net-(D75-C)") (class "Default")
      (node (ref "D75") (pin "2") (pinfunction "C_2") (pintype "passive"))
      (node (ref "R25") (pin "1") (pinfunction "1_1") (pintype "passive"))
    )
  )
)
